# CPU-board-Sheet1-multi.net
KiCad netlist of a schematic drawn in Altium Designer
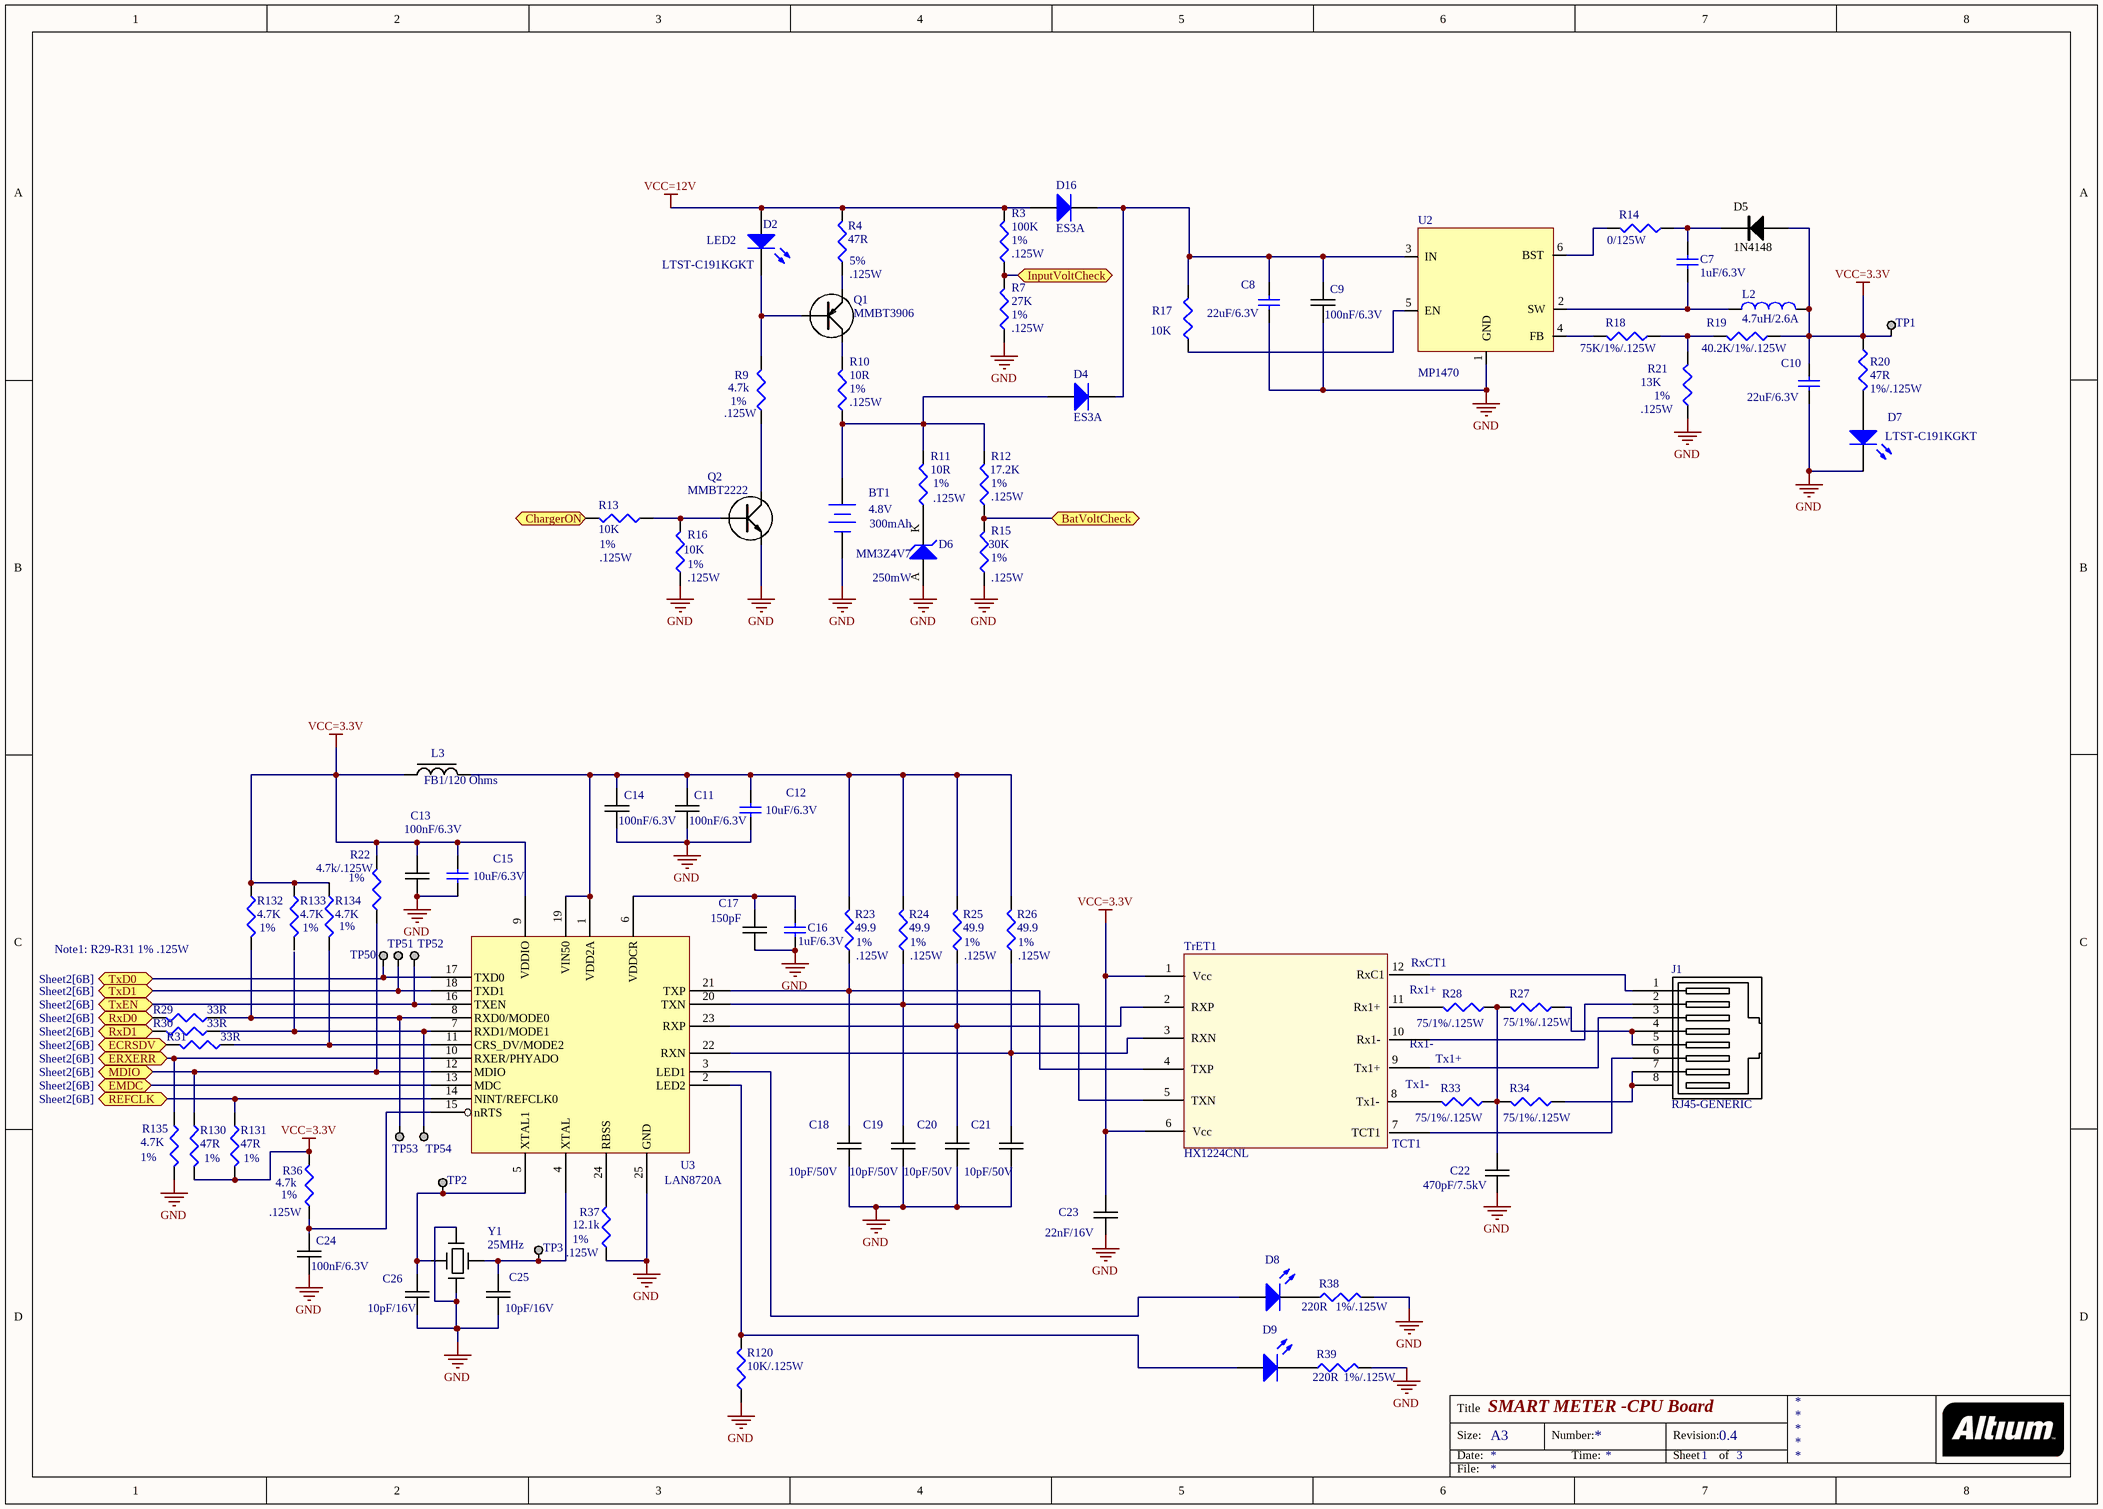
[diagram p0: CPU-board-Sheet1-multi.SchDoc]

(export (version "E")
  (design (tool "Eeschema 10.0.6"))
  (components
    (comp (ref "BT1")
      (value "4.8V")
      (footprint "BAT-2")
      (description "Multicell Battery")
      (fields
        (field (name "MANUFACTURER") "Guangdong, China (Mainland)")
        (field (name "PUBLISHER") "sunbangpower.en.alibaba.com")
      )
      (libsource (lib "Miscellaneous Devices") (part "Battery"))
    )
    (comp (ref "C7")
      (value "1uF/6.3V")
      (footprint "0402C-GENERIC")
      (description "Capacitor")
      (fields (field (name "MANUFACTURER") "Murata") (field (name "PUBLISHER") "Altium Limited"))
      (libsource (lib "Miscellaneous Devices") (part "Cap"))
    )
    (comp (ref "C8")
      (value "22uF/6.3V")
      (footprint "1206C-GENERIC")
      (description "Capacitor")
      (fields (field (name "MANUFACTURER") "Murata") (field (name "PUBLISHER") "Altium Limited"))
      (libsource (lib "Miscellaneous Devices") (part "Cap"))
    )
    (comp (ref "C9")
      (value "100nF/6.3V")
      (footprint "0402C-GENERIC")
      (description "CAPACITOR 0805 CERAMIC")
      (fields (field (name "MANUFACTURER") "Taiyo Yuden"))
      (libsource (lib "vh_altium_library") (part "0805C-18PF-50V-C0G-JOH"))
    )
    (comp (ref "C10")
      (value "22uF/6.3V")
      (footprint "1206C-GENERIC")
      (description "Capacitor")
      (fields (field (name "MANUFACTURER") "Murata") (field (name "PUBLISHER") "Altium Limited"))
      (libsource (lib "Miscellaneous Devices") (part "Cap"))
    )
    (comp (ref "C11")
      (value "100nF/6.3V")
      (footprint "0402C-GENERIC")
      (description "CAPACITOR 0805 CERAMIC")
      (fields (field (name "MANUFACTURER") "Taiyo Yuden"))
      (libsource (lib "vh_altium_library") (part "0805C-18PF-50V-C0G-JOH"))
    )
    (comp (ref "C12")
      (value "10uF/6.3V")
      (footprint "0402C-GENERIC")
      (description "Capacitor")
      (fields (field (name "MANUFACTURER") "Murata") (field (name "PUBLISHER") "Altium Limited"))
      (libsource (lib "Miscellaneous Devices") (part "Cap"))
    )
    (comp (ref "C13")
      (value "100nF/6.3V")
      (footprint "0402C-GENERIC")
      (description "CAPACITOR 0805 CERAMIC")
      (fields (field (name "MANUFACTURER") "Taiyo Yuden"))
      (libsource (lib "vh_altium_library") (part "0805C-18PF-50V-C0G-JOH"))
    )
    (comp (ref "C14")
      (value "100nF/6.3V")
      (footprint "0402C-GENERIC")
      (description "CAPACITOR 0805 CERAMIC")
      (fields (field (name "MANUFACTURER") "Taiyo Yuden"))
      (libsource (lib "vh_altium_library") (part "0805C-18PF-50V-C0G-JOH"))
    )
    (comp (ref "C15")
      (value "10uF/6.3V")
      (footprint "0402C-GENERIC")
      (description "Capacitor")
      (fields (field (name "MANUFACTURER") "Murata") (field (name "PUBLISHER") "Altium Limited"))
      (libsource (lib "Miscellaneous Devices") (part "Cap"))
    )
    (comp (ref "C16")
      (value "1uF/6.3V")
      (footprint "0402C-GENERIC")
      (description "Capacitor")
      (fields (field (name "MANUFACTURER") "Murata") (field (name "PUBLISHER") "Altium Limited"))
      (libsource (lib "Miscellaneous Devices") (part "Cap"))
    )
    (comp (ref "C17")
      (value "150pF")
      (footprint "0402C-GENERIC")
      (description "CAPACITOR 0805 CERAMIC")
      (fields (field (name "MANUFACTURER") "Wurth Electronics"))
      (libsource (lib "vh_altium_library") (part "0805C-18PF-50V-C0G-JOH"))
    )
    (comp (ref "C18")
      (value "10pF/50V")
      (footprint "0402C-GENERIC")
      (description "CAPACITOR 0805 CERAMIC")
      (fields (field (name "MANUFACTURER") "Murata"))
      (libsource (lib "vh_altium_library") (part "0805C-18PF-50V-C0G-JOH"))
    )
    (comp (ref "C19")
      (value "10pF/50V")
      (footprint "0402C-GENERIC")
      (description "CAPACITOR 0805 CERAMIC")
      (fields (field (name "MANUFACTURER") "Murata"))
      (libsource (lib "vh_altium_library") (part "0805C-18PF-50V-C0G-JOH"))
    )
    (comp (ref "C20")
      (value "10pF/50V")
      (footprint "0402C-GENERIC")
      (description "CAPACITOR 0805 CERAMIC")
      (fields (field (name "MANUFACTURER") "Murata"))
      (libsource (lib "vh_altium_library") (part "0805C-18PF-50V-C0G-JOH"))
    )
    (comp (ref "C21")
      (value "10pF/50V")
      (footprint "0402C-GENERIC")
      (description "CAPACITOR 0805 CERAMIC")
      (fields (field (name "MANUFACTURER") "Murata"))
      (libsource (lib "vh_altium_library") (part "0805C-18PF-50V-C0G-JOH"))
    )
    (comp (ref "C22")
      (value "470pF/7.5kV")
      (footprint "1808")
      (description "CAPACITOR 1808CERAMIC")
      (fields (field (name "MANUFACTURER") "Murata"))
      (libsource (lib "vh_altium_library") (part "0805C-18PF-50V-C0G-JOH"))
    )
    (comp (ref "C23")
      (value "22nF/16V")
      (footprint "0402C-GENERIC")
      (description "CAPACITOR 0805 CERAMIC")
      (fields (field (name "MANUFACTURER") "Murata Electronics"))
      (libsource (lib "vh_altium_library") (part "0805C-18PF-50V-C0G-JOH"))
    )
    (comp (ref "C24")
      (value "100nF/6.3V")
      (footprint "0402C-GENERIC")
      (description "CAPACITOR 0805 CERAMIC")
      (fields (field (name "MANUFACTURER") "Taiyo Yuden"))
      (libsource (lib "vh_altium_library") (part "0805C-18PF-50V-C0G-JOH"))
    )
    (comp (ref "C25")
      (value "10pF/16V")
      (footprint "0402C-GENERIC")
      (description "CAPACITOR 0805 CERAMIC")
      (fields (field (name "MANUFACTURER") "Murata"))
      (libsource (lib "vh_altium_library") (part "0805C-18PF-50V-C0G-JOH"))
    )
    (comp (ref "C26")
      (value "10pF/16V")
      (footprint "0402C-GENERIC")
      (description "CAPACITOR 0805 CERAMIC")
      (fields (field (name "MANUFACTURER") "Murata"))
      (libsource (lib "vh_altium_library") (part "0805C-18PF-50V-C0G-JOH"))
    )
    (comp (ref "D2")
      (value "LED2")
      (footprint "LED-SM")
      (description "Typical RED, GREEN, YELLOW, AMBER GaAs LED")
      (fields (field (name "MANUFACTURER") "Lite-On Inc") (field (name "PUBLISHER") "Altium Limited"))
      (libsource (lib "Miscellaneous Devices") (part "LED2"))
    )
    (comp (ref "D4")
      (value "ES3A")
      (footprint "DO214AA")
      (description "1 Amp General Purpose Rectifier")
      (fields (field (name "MANUFACTURER") "Fairchild Co") (field (name "PUBLISHER") "Altium Limited"))
      (libsource (lib "Miscellaneous Devices") (part "Diode 1N4007"))
    )
    (comp (ref "D5")
      (value "1N4148")
      (footprint "SOD-123")
      (description "1N4001")
      (fields (field (name "MANUFACTURER") "Vishay"))
      (libsource (lib "vh_altium_library") (part "1N4001"))
    )
    (comp (ref "D6")
      (value "MM3Z4V7")
      (footprint "SOT23-DIODE")
      (description "Zener Diode")
      (fields (field (name "MANUFACTURER") "Fairchild Semi") (field (name "PUBLISHER") "Altium Limited"))
      (libsource (lib "Miscellaneous Devices") (part "D Zener"))
    )
    (comp (ref "D7")
      (value "LED2")
      (footprint "LED-SM")
      (description "Typical RED, GREEN, YELLOW, AMBER GaAs LED")
      (fields (field (name "MANUFACTURER") "Lite-On Inc") (field (name "PUBLISHER") "Altium Limited"))
      (libsource (lib "Miscellaneous Devices") (part "LED2"))
    )
    (comp (ref "D8")
      (value "LED2")
      (footprint "LED-SM")
      (description "Typical RED, GREEN, YELLOW, AMBER GaAs LED")
      (fields (field (name "MANUFACTURER") "Lite-On Inc") (field (name "PUBLISHER") "Altium Limited"))
      (libsource (lib "Miscellaneous Devices") (part "LED2"))
    )
    (comp (ref "D9")
      (value "LED2")
      (footprint "LED-SM")
      (description "Typical RED, GREEN, YELLOW, AMBER GaAs LED")
      (fields (field (name "MANUFACTURER") "Lite-On Inc") (field (name "PUBLISHER") "Altium Limited"))
      (libsource (lib "Miscellaneous Devices") (part "LED2"))
    )
    (comp (ref "D16")
      (value "ES3A")
      (footprint "DO214AA")
      (description "1 Amp General Purpose Rectifier")
      (fields (field (name "MANUFACTURER") "Fairchild Co") (field (name "PUBLISHER") "Altium Limited"))
      (libsource (lib "Miscellaneous Devices") (part "Diode 1N4007"))
    )
    (comp (ref "J1")
      (value "RJ45-GENERIC")
      (footprint "RJ45-8/8")
      (description "GENERIC RJ45 CONNECTOR 8 PIN")
      (fields (field (name "MANUFACTURER") "Assman WSW Components"))
      (libsource (lib "vh_altium_library") (part "RJ45-GENERIC"))
    )
    (comp (ref "L2")
      (value "4.7uH/2.6A")
      (footprint "Inductor 4.7/6.8")
      (description "Inductor")
      (fields (field (name "MANUFACTURER") "Bourns") (field (name "PUBLISHER") "Altium Limited"))
      (libsource (lib "Miscellaneous Devices") (part "Inductor"))
    )
    (comp (ref "L3")
      (value "FB1/120 Ohms")
      (footprint "0603C-2U2")
      (description "1239AS-H-1R0N")
      (fields (field (name "MANUFACTURER") "Murata Electronics"))
      (libsource (lib "SMD Magnetics-SM") (part "1U-1239AS-TOKO"))
    )
    (comp (ref "Q1")
      (value "MMBT3906")
      (footprint "SOT23-BCE")
      (description "GENERIC PNP BIPOLAR TRANSISTOR")
      (fields (field (name "MANUFACTURER") "On Semi"))
      (libsource (lib "generic") (part "PNP-GENERIC"))
    )
    (comp (ref "Q2")
      (value "MMBT2222")
      (footprint "MMBT2222")
      (description "BC847 SMALL SIGNAL NPN TRANSISTOR")
      (fields (field (name "MANUFACTURER") "Diodes  Inc."))
      (libsource (lib "vh_altium_library") (part "MMBT2222"))
    )
    (comp (ref "R3")
      (value "100K")
      (footprint "0402R-TBD")
      (description "Resistor")
      (fields (field (name "MANUFACTURER") "Panasonic") (field (name "PUBLISHER") "Altium Limited"))
      (libsource (lib "Miscellaneous Devices") (part "Res3"))
    )
    (comp (ref "R4")
      (value "47R")
      (footprint "0402R-TBD")
      (description "Resistor")
      (fields (field (name "PUBLISHER") "Altium Limited"))
      (libsource (lib "Miscellaneous Devices") (part "Res3"))
    )
    (comp (ref "R7")
      (value "27K")
      (footprint "0402R-TBD")
      (description "Resistor")
      (fields (field (name "MANUFACTURER") "Panasonic") (field (name "PUBLISHER") "Altium Limited"))
      (libsource (lib "Miscellaneous Devices") (part "Res3"))
    )
    (comp (ref "R9")
      (value "4.7k")
      (footprint "0402R-TBD")
      (description "Resistor")
      (fields (field (name "MANUFACTURER") "Panasonic") (field (name "PUBLISHER") "Altium Limited"))
      (libsource (lib "Miscellaneous Devices") (part "Res3"))
    )
    (comp (ref "R10")
      (value "10R")
      (footprint "0402R-TBD")
      (description "Resistor")
      (fields (field (name "MANUFACTURER") "Panasonic") (field (name "PUBLISHER") "Altium Limited"))
      (libsource (lib "Miscellaneous Devices") (part "Res3"))
    )
    (comp (ref "R11")
      (value "10R")
      (footprint "0402R-TBD")
      (description "Resistor")
      (fields (field (name "MANUFACTURER") "Panasonic") (field (name "PUBLISHER") "Altium Limited"))
      (libsource (lib "Miscellaneous Devices") (part "Res3"))
    )
    (comp (ref "R12")
      (value "17.2K")
      (footprint "0402R-TBD")
      (description "Resistor")
      (fields (field (name "MANUFACTURER") "Vishay Dale") (field (name "PUBLISHER") "Altium Limited"))
      (libsource (lib "Miscellaneous Devices") (part "Res3"))
    )
    (comp (ref "R13")
      (value "10K")
      (footprint "0402R-TBD")
      (description "Resistor")
      (fields (field (name "MANUFACTURER") "Panasonic") (field (name "PUBLISHER") "Altium Limited"))
      (libsource (lib "Miscellaneous Devices") (part "Res3"))
    )
    (comp (ref "R14")
      (value "0/125W")
      (footprint "0402C-GENERIC")
      (description "Resistor")
      (fields (field (name "MANUFACTURER") "Vishay Dale") (field (name "PUBLISHER") "Altium Limited"))
      (libsource (lib "Miscellaneous Devices") (part "Res3"))
    )
    (comp (ref "R15")
      (value "30K")
      (footprint "0402R-TBD")
      (description "Resistor")
      (fields (field (name "MANUFACTURER") "Panasonic") (field (name "PUBLISHER") "Altium Limited"))
      (libsource (lib "Miscellaneous Devices") (part "Res3"))
    )
    (comp (ref "R16")
      (value "10K")
      (footprint "0402R-TBD")
      (description "Resistor")
      (fields (field (name "MANUFACTURER") "Panasonic") (field (name "PUBLISHER") "Altium Limited"))
      (libsource (lib "Miscellaneous Devices") (part "Res3"))
    )
    (comp (ref "R17")
      (value "10K")
      (footprint "0402R-TBD")
      (description "Resistor")
      (fields (field (name "MANUFACTURER") "Panasonic") (field (name "PUBLISHER") "Altium Limited"))
      (libsource (lib "Miscellaneous Devices") (part "Res3"))
    )
    (comp (ref "R18")
      (value "75K/1%/.125W")
      (footprint "0402C-TBD")
      (description "Resistor")
      (fields (field (name "MANUFACTURER") "Panasonic") (field (name "PUBLISHER") "Altium Limited"))
      (libsource (lib "Miscellaneous Devices") (part "Res3"))
    )
    (comp (ref "R19")
      (value "40.2K/1%/.125W")
      (footprint "0402R-TBD")
      (description "Resistor")
      (fields (field (name "MANUFACTURER") "Panasonic") (field (name "PUBLISHER") "Altium Limited"))
      (libsource (lib "Miscellaneous Devices") (part "Res3"))
    )
    (comp (ref "R20")
      (value "47R")
      (footprint "0402R-TBD")
      (description "Resistor")
      (fields (field (name "PUBLISHER") "Altium Limited"))
      (libsource (lib "Miscellaneous Devices") (part "Res3"))
    )
    (comp (ref "R21")
      (value "13K")
      (footprint "0402R-TBD")
      (description "Resistor")
      (fields (field (name "MANUFACTURER") "Panasonic") (field (name "PUBLISHER") "Altium Limited"))
      (libsource (lib "Miscellaneous Devices") (part "Res3"))
    )
    (comp (ref "R22")
      (value "4.7k/.125W")
      (footprint "0402R-TBD")
      (description "Resistor")
      (fields (field (name "MANUFACTURER") "Panasonic") (field (name "PUBLISHER") "Altium Limited"))
      (libsource (lib "Miscellaneous Devices") (part "Res3"))
    )
    (comp (ref "R23")
      (value "49.9")
      (footprint "0402R-TBD")
      (description "Resistor")
      (fields (field (name "MANUFACTURER") "Panasonic") (field (name "PUBLISHER") "Altium Limited"))
      (libsource (lib "Miscellaneous Devices") (part "Res3"))
    )
    (comp (ref "R24")
      (value "49.9")
      (footprint "0402R-TBD")
      (description "Resistor")
      (fields (field (name "MANUFACTURER") "Panasonic") (field (name "PUBLISHER") "Altium Limited"))
      (libsource (lib "Miscellaneous Devices") (part "Res3"))
    )
    (comp (ref "R25")
      (value "49.9")
      (footprint "0402R-TBD")
      (description "Resistor")
      (fields (field (name "MANUFACTURER") "Panasonic") (field (name "PUBLISHER") "Altium Limited"))
      (libsource (lib "Miscellaneous Devices") (part "Res3"))
    )
    (comp (ref "R26")
      (value "49.9")
      (footprint "0402R-TBD")
      (description "Resistor")
      (fields (field (name "MANUFACTURER") "Panasonic") (field (name "PUBLISHER") "Altium Limited"))
      (libsource (lib "Miscellaneous Devices") (part "Res3"))
    )
    (comp (ref "R27")
      (value "75/1%/.125W")
      (footprint "0402R-TBD")
      (description "Resistor")
      (fields (field (name "MANUFACTURER") "Panasonic") (field (name "PUBLISHER") "Altium Limited"))
      (libsource (lib "Miscellaneous Devices") (part "Res3"))
    )
    (comp (ref "R28")
      (value "75/1%/.125W")
      (footprint "0402R-TBD")
      (description "Resistor")
      (fields (field (name "MANUFACTURER") "Panasonic") (field (name "PUBLISHER") "Altium Limited"))
      (libsource (lib "Miscellaneous Devices") (part "Res3"))
    )
    (comp (ref "R29")
      (value "33R")
      (footprint "0402R-TBD")
      (description "Resistor")
      (fields (field (name "MANUFACTURER") "Panasonic") (field (name "PUBLISHER") "Altium Limited"))
      (libsource (lib "Miscellaneous Devices") (part "Res3"))
    )
    (comp (ref "R30")
      (value "33R")
      (footprint "0402R-TBD")
      (description "Resistor")
      (fields (field (name "MANUFACTURER") "Panasonic") (field (name "PUBLISHER") "Altium Limited"))
      (libsource (lib "Miscellaneous Devices") (part "Res3"))
    )
    (comp (ref "R31")
      (value "33R")
      (footprint "0402R-TBD")
      (description "Resistor")
      (fields (field (name "MANUFACTURER") "Panasonic") (field (name "PUBLISHER") "Altium Limited"))
      (libsource (lib "Miscellaneous Devices") (part "Res3"))
    )
    (comp (ref "R33")
      (value "75/1%/.125W")
      (footprint "0402R-TBD")
      (description "Resistor")
      (fields (field (name "MANUFACTURER") "Panasonic") (field (name "PUBLISHER") "Altium Limited"))
      (libsource (lib "Miscellaneous Devices") (part "Res3"))
    )
    (comp (ref "R34")
      (value "75/1%/.125W")
      (footprint "0402R-TBD")
      (description "Resistor")
      (fields (field (name "MANUFACTURER") "Panasonic") (field (name "PUBLISHER") "Altium Limited"))
      (libsource (lib "Miscellaneous Devices") (part "Res3"))
    )
    (comp (ref "R36")
      (value "4.7k")
      (footprint "0402R-TBD")
      (description "Resistor")
      (fields (field (name "MANUFACTURER") "Panasonic") (field (name "PUBLISHER") "Altium Limited"))
      (libsource (lib "Miscellaneous Devices") (part "Res3"))
    )
    (comp (ref "R37")
      (value "12.1k")
      (footprint "0402R-TBD")
      (description "Resistor")
      (fields (field (name "MANUFACTURER") "Panasonic") (field (name "PUBLISHER") "Altium Limited"))
      (libsource (lib "Miscellaneous Devices") (part "Res3"))
    )
    (comp (ref "R38")
      (value "220R")
      (footprint "0402R-TBD")
      (description "Resistor")
      (fields (field (name "MANUFACTURER") "Panasonic") (field (name "PUBLISHER") "Altium Limited"))
      (libsource (lib "Miscellaneous Devices") (part "Res3"))
    )
    (comp (ref "R39")
      (value "220R")
      (footprint "0402R-TBD")
      (description "Resistor")
      (fields (field (name "MANUFACTURER") "Panasonic") (field (name "PUBLISHER") "Altium Limited"))
      (libsource (lib "Miscellaneous Devices") (part "Res3"))
    )
    (comp (ref "R120")
      (value "10K/.125W")
      (footprint "0402R-TBD")
      (description "Resistor")
      (fields (field (name "MANUFACTURER") "Panasonic") (field (name "PUBLISHER") "Altium Limited"))
      (libsource (lib "Miscellaneous Devices") (part "Res3"))
    )
    (comp (ref "R130")
      (value "47R")
      (footprint "0402R-TBD")
      (description "Resistor")
      (fields (field (name "MANUFACTURER") "Panasonic") (field (name "PUBLISHER") "Altium Limited"))
      (libsource (lib "Miscellaneous Devices") (part "Res3"))
    )
    (comp (ref "R131")
      (value "47R")
      (footprint "0402R-TBD")
      (description "Resistor")
      (fields (field (name "MANUFACTURER") "Panasonic") (field (name "PUBLISHER") "Altium Limited"))
      (libsource (lib "Miscellaneous Devices") (part "Res3"))
    )
    (comp (ref "R132")
      (value "4.7K")
      (footprint "0402R-TBD")
      (description "Resistor")
      (fields (field (name "MANUFACTURER") "Panasonic") (field (name "PUBLISHER") "Altium Limited"))
      (libsource (lib "Miscellaneous Devices") (part "Res3"))
    )
    (comp (ref "R133")
      (value "4.7K")
      (footprint "0402R-TBD")
      (description "Resistor")
      (fields (field (name "MANUFACTURER") "Panasonic") (field (name "PUBLISHER") "Altium Limited"))
      (libsource (lib "Miscellaneous Devices") (part "Res3"))
    )
    (comp (ref "R134")
      (value "4.7K")
      (footprint "0402R-TBD")
      (description "Resistor")
      (fields (field (name "MANUFACTURER") "Panasonic") (field (name "PUBLISHER") "Altium Limited"))
      (libsource (lib "Miscellaneous Devices") (part "Res3"))
    )
    (comp (ref "R135")
      (value "4.7K")
      (footprint "0402R-TBD")
      (description "Resistor")
      (fields (field (name "MANUFACTURER") "Panasonic") (field (name "PUBLISHER") "Altium Limited"))
      (libsource (lib "Miscellaneous Devices") (part "Res3"))
    )
    (comp (ref "TP1")
      (value "TESTPOINT")
      (footprint "TESTPOINT")
      (description "TESTPOINT SCOPE GRABBER")
      (fields
        (field (name "MANUFACTURER PART NUMBER") "5010")
        (field (name "MANUFACTURER") "Keystone Electronics")
      )
      (libsource (lib "vh_altium_library") (part "TESTPOINT"))
    )
    (comp (ref "TP2")
      (value "TESTPOINT")
      (footprint "TESTPOINT")
      (description "TESTPOINT SCOPE GRABBER")
      (fields
        (field (name "MANUFACTURER PART NUMBER") "5010")
        (field (name "MANUFACTURER") "Keystone Electronics")
      )
      (libsource (lib "vh_altium_library") (part "TESTPOINT"))
    )
    (comp (ref "TP3")
      (value "TESTPOINT")
      (footprint "TESTPOINT")
      (description "TESTPOINT SCOPE GRABBER")
      (fields
        (field (name "MANUFACTURER PART NUMBER") "5010")
        (field (name "MANUFACTURER") "Keystone Electronics")
      )
      (libsource (lib "vh_altium_library") (part "TESTPOINT"))
    )
    (comp (ref "TP50")
      (value "TESTPOINT")
      (footprint "TESTPOINT")
      (description "TESTPOINT SCOPE GRABBER")
      (fields
        (field (name "MANUFACTURER PART NUMBER") "5010")
        (field (name "MANUFACTURER") "Keystone Electronics")
      )
      (libsource (lib "vh_altium_library") (part "TESTPOINT"))
    )
    (comp (ref "TP51")
      (value "TESTPOINT")
      (footprint "TESTPOINT")
      (description "TESTPOINT SCOPE GRABBER")
      (fields
        (field (name "MANUFACTURER PART NUMBER") "5010")
        (field (name "MANUFACTURER") "Keystone Electronics")
      )
      (libsource (lib "vh_altium_library") (part "TESTPOINT"))
    )
    (comp (ref "TP52")
      (value "TESTPOINT")
      (footprint "TESTPOINT")
      (description "TESTPOINT SCOPE GRABBER")
      (fields
        (field (name "MANUFACTURER PART NUMBER") "5010")
        (field (name "MANUFACTURER") "Keystone Electronics")
      )
      (libsource (lib "vh_altium_library") (part "TESTPOINT"))
    )
    (comp (ref "TP53")
      (value "TESTPOINT")
      (footprint "TESTPOINT")
      (description "TESTPOINT SCOPE GRABBER")
      (fields
        (field (name "MANUFACTURER PART NUMBER") "5010")
        (field (name "MANUFACTURER") "Keystone Electronics")
      )
      (libsource (lib "vh_altium_library") (part "TESTPOINT"))
    )
    (comp (ref "TP54")
      (value "TESTPOINT")
      (footprint "TESTPOINT")
      (description "TESTPOINT SCOPE GRABBER")
      (fields
        (field (name "MANUFACTURER PART NUMBER") "5010")
        (field (name "MANUFACTURER") "Keystone Electronics")
      )
      (libsource (lib "vh_altium_library") (part "TESTPOINT"))
    )
    (comp (ref "TrET1") (value "HX1224CNL") (libsource (lib "SMLib") (part "hx1224nl")))
    (comp (ref "U2")
      (value "MP1470")
      (footprint "MP1470")
      (fields (field (name "MANUFACTURER") "MPS Inc"))
      (libsource (lib "SMLib") (part "MP1470"))
    )
    (comp (ref "U3")
      (value "LAN8720A")
      (footprint "Atmel Multimedia:QFN24_4X4_N")
      (fields (field (name "MANUFACTURER") "Microchip"))
      (libsource (lib "SMLib") (part "LAN8720"))
    )
    (comp (ref "Y1")
      (value "25MHz")
      (footprint "CeramicResonator8-16MHZ")
      (description "25MHz CRYSTAL HC49US SHORT BODY")
      (fields (field (name "MANUFACTURER") "KDS DAISHINKU.Corp"))
      (libsource (lib "Crystals") (part "12MC-HC49US-7MM"))
    )
  )
  (nets
    (net (code "1") (name "/BatVoltCheck") (class "Default")
      (node (ref "R12") (pin "1") (pinfunction "1_1") (pintype "passive"))
      (node (ref "R15") (pin "2") (pinfunction "2_2") (pintype "passive"))
    )
    (net (code "2") (name "/ChargerON") (class "Default")
      (node (ref "R13") (pin "2") (pinfunction "2_2") (pintype "passive"))
    )
    (net (code "3") (name "/ECRSDV") (class "Default")
      (node (ref "R31") (pin "2") (pinfunction "2_2") (pintype "passive"))
    )
    (net (code "4") (name "/EMDC") (class "Default")
      (node (ref "U3") (pin "13") (pinfunction "MDC_13") (pintype "passive"))
    )
    (net (code "5") (name "/ERXERR") (class "Default")
      (node (ref "R135") (pin "1") (pinfunction "1_1") (pintype "passive"))
      (node (ref "U3") (pin "10") (pinfunction "RXER/PHYADO_10") (pintype "passive"))
    )
    (net (code "6") (name "/InputVoltCheck") (class "Default")
      (node (ref "R3") (pin "1") (pinfunction "1_1") (pintype "passive"))
      (node (ref "R7") (pin "2") (pinfunction "2_2") (pintype "passive"))
    )
    (net (code "7") (name "/MDIO") (class "Default")
      (node (ref "R130") (pin "1") (pinfunction "1_1") (pintype "passive"))
      (node (ref "R22") (pin "1") (pinfunction "1_1") (pintype "passive"))
      (node (ref "U3") (pin "12") (pinfunction "MDIO_12") (pintype "passive"))
    )
    (net (code "8") (name "/REFCLK") (class "Default")
      (node (ref "R131") (pin "1") (pinfunction "1_1") (pintype "passive"))
      (node (ref "U3") (pin "14") (pinfunction "NINT/REFCLK0_14") (pintype "passive"))
    )
    (net (code "9") (name "/RxD0") (class "Default")
      (node (ref "R29") (pin "2") (pinfunction "2_2") (pintype "passive"))
    )
    (net (code "10") (name "/RxD1") (class "Default")
      (node (ref "R30") (pin "2") (pinfunction "2_2") (pintype "passive"))
    )
    (net (code "11") (name "/TxD0") (class "Default")
      (node (ref "TP50") (pin "1") (pinfunction "1_1") (pintype "passive"))
      (node (ref "U3") (pin "17") (pinfunction "TXD0_17") (pintype "passive"))
    )
    (net (code "12") (name "/TxD1") (class "Default")
      (node (ref "TP51") (pin "1") (pinfunction "1_1") (pintype "passive"))
      (node (ref "U3") (pin "18") (pinfunction "TXD1_18") (pintype "passive"))
    )
    (net (code "13") (name "/TxEN") (class "Default")
      (node (ref "TP52") (pin "1") (pinfunction "1_1") (pintype "passive"))
      (node (ref "U3") (pin "16") (pinfunction "TXEN_16") (pintype "passive"))
    )
    (net (code "14") (name "GND") (class "Default")
      (node (ref "BT1") (pin "2") (pinfunction "-_2") (pintype "passive"))
      (node (ref "C10") (pin "2") (pinfunction "2_2") (pintype "passive"))
      (node (ref "C11") (pin "2") (pintype "passive"))
      (node (ref "C12") (pin "2") (pinfunction "2_2") (pintype "passive"))
      (node (ref "C13") (pin "2") (pintype "passive"))
      (node (ref "C14") (pin "2") (pintype "passive"))
      (node (ref "C15") (pin "2") (pinfunction "2_2") (pintype "passive"))
      (node (ref "C16") (pin "1") (pinfunction "1_1") (pintype "passive"))
      (node (ref "C17") (pin "2") (pintype "passive"))
      (node (ref "C18") (pin "2") (pintype "passive"))
      (node (ref "C19") (pin "2") (pintype "passive"))
      (node (ref "C20") (pin "2") (pintype "passive"))
      (node (ref "C21") (pin "2") (pintype "passive"))
      (node (ref "C22") (pin "2") (pintype "passive"))
      (node (ref "C23") (pin "2") (pintype "passive"))
      (node (ref "C24") (pin "2") (pintype "passive"))
      (node (ref "C25") (pin "2") (pintype "passive"))
      (node (ref "C26") (pin "2") (pintype "passive"))
      (node (ref "C8") (pin "2") (pinfunction "2_2") (pintype "passive"))
      (node (ref "C9") (pin "2") (pintype "passive"))
      (node (ref "D6") (pin "A") (pinfunction "A_A") (pintype "passive"))
      (node (ref "D7") (pin "2") (pinfunction "K_2") (pintype "passive"))
      (node (ref "Q2") (pin "E") (pintype "passive"))
      (node (ref "R120") (pin "1") (pinfunction "1_1") (pintype "passive"))
      (node (ref "R135") (pin "2") (pinfunction "2_2") (pintype "passive"))
      (node (ref "R15") (pin "1") (pinfunction "1_1") (pintype "passive"))
      (node (ref "R16") (pin "1") (pinfunction "1_1") (pintype "passive"))
      (node (ref "R21") (pin "1") (pinfunction "1_1") (pintype "passive"))
      (node (ref "R37") (pin "1") (pinfunction "1_1") (pintype "passive"))
      (node (ref "R38") (pin "2") (pinfunction "2_2") (pintype "passive"))
      (node (ref "R39") (pin "2") (pinfunction "2_2") (pintype "passive"))
      (node (ref "R7") (pin "1") (pinfunction "1_1") (pintype "passive"))
      (node (ref "U2") (pin "1") (pinfunction "GND_1") (pintype "passive"))
      (node (ref "U3") (pin "25") (pinfunction "GND_25") (pintype "passive"))
      (node (ref "Y1") (pin "2") (pintype "passive"))
      (node (ref "Y1") (pin "4") (pintype "passive"))
    )
    (net (code "15") (name "Net-(BT1-+)") (class "Default")
      (node (ref "BT1") (pin "1") (pinfunction "+_1") (pintype "passive"))
      (node (ref "D4") (pin "1") (pinfunction "A_1") (pintype "passive"))
      (node (ref "R10") (pin "1") (pinfunction "1_1") (pintype "passive"))
      (node (ref "R11") (pin "2") (pinfunction "2_2") (pintype "passive"))
      (node (ref "R12") (pin "2") (pinfunction "2_2") (pintype "passive"))
    )
    (net (code "16") (name "Net-(C7-Pad2)") (class "Default")
      (node (ref "C7") (pin "2") (pinfunction "2_2") (pintype "passive"))
      (node (ref "D5") (pin "K") (pinfunction "K_K") (pintype "passive"))
      (node (ref "R14") (pin "1") (pinfunction "1_1") (pintype "passive"))
    )
    (net (code "17") (name "Net-(C22-Pad1)") (class "Default")
      (node (ref "C22") (pin "1") (pintype "passive"))
      (node (ref "R27") (pin "2") (pinfunction "2_2") (pintype "passive"))
      (node (ref "R28") (pin "1") (pinfunction "1_1") (pintype "passive"))
      (node (ref "R33") (pin "1") (pinfunction "1_1") (pintype "passive"))
      (node (ref "R34") (pin "2") (pinfunction "2_2") (pintype "passive"))
    )
    (net (code "18") (name "Net-(D2-K)") (class "Default")
      (node (ref "D2") (pin "2") (pinfunction "K_2") (pintype "passive"))
      (node (ref "Q1") (pin "B") (pintype "passive"))
      (node (ref "R9") (pin "2") (pinfunction "2_2") (pintype "passive"))
    )
    (net (code "19") (name "Net-(D6-PadK)") (class "Default")
      (node (ref "D6") (pin "K") (pinfunction "K_K") (pintype "passive"))
      (node (ref "R11") (pin "1") (pinfunction "1_1") (pintype "passive"))
    )
    (net (code "20") (name "Net-(D7-A)") (class "Default")
      (node (ref "D7") (pin "1") (pinfunction "A_1") (pintype "passive"))
      (node (ref "R20") (pin "2") (pinfunction "2_2") (pintype "passive"))
    )
    (net (code "21") (name "Net-(D8-A)") (class "Default")
      (node (ref "D8") (pin "1") (pinfunction "A_1") (pintype "passive"))
      (node (ref "U3") (pin "3") (pinfunction "LED1_3") (pintype "passive"))
    )
    (net (code "22") (name "Net-(D8-K)") (class "Default")
      (node (ref "D8") (pin "2") (pinfunction "K_2") (pintype "passive"))
      (node (ref "R38") (pin "1") (pinfunction "1_1") (pintype "passive"))
    )
    (net (code "23") (name "Net-(D9-A)") (class "Default")
      (node (ref "D9") (pin "1") (pinfunction "A_1") (pintype "passive"))
      (node (ref "R120") (pin "2") (pinfunction "2_2") (pintype "passive"))
      (node (ref "U3") (pin "2") (pinfunction "LED2_2") (pintype "passive"))
    )
    (net (code "24") (name "Net-(D9-K)") (class "Default")
      (node (ref "D9") (pin "2") (pinfunction "K_2") (pintype "passive"))
      (node (ref "R39") (pin "1") (pinfunction "1_1") (pintype "passive"))
    )
    (net (code "25") (name "Net-(D16-K)") (class "Default")
      (node (ref "C8") (pin "1") (pinfunction "1_1") (pintype "passive"))
      (node (ref "C9") (pin "1") (pintype "passive"))
      (node (ref "D16") (pin "2") (pinfunction "K_2") (pintype "passive"))
      (node (ref "D4") (pin "2") (pinfunction "K_2") (pintype "passive"))
      (node (ref "R17") (pin "2") (pinfunction "2_2") (pintype "passive"))
      (node (ref "U2") (pin "3") (pinfunction "IN_3") (pintype "passive"))
    )
    (net (code "26") (name "Net-(J1-Pad4)") (class "Default")
      (node (ref "J1") (pin "4") (pintype "passive"))
      (node (ref "J1") (pin "5") (pintype "passive"))
      (node (ref "R27") (pin "1") (pinfunction "1_1") (pintype "passive"))
    )
    (net (code "27") (name "Net-(J1-Pad7)") (class "Default")
      (node (ref "J1") (pin "7") (pintype "passive"))
      (node (ref "J1") (pin "8") (pintype "passive"))
      (node (ref "R34") (pin "1") (pinfunction "1_1") (pintype "passive"))
    )
    (net (code "28") (name "Net-(Q1-PadC)") (class "Default")
      (node (ref "Q1") (pin "C") (pintype "passive"))
      (node (ref "R10") (pin "2") (pinfunction "2_2") (pintype "passive"))
    )
    (net (code "29") (name "Net-(Q1-PadE)") (class "Default")
      (node (ref "Q1") (pin "E") (pintype "passive"))
      (node (ref "R4") (pin "1") (pinfunction "1_1") (pintype "passive"))
    )
    (net (code "30") (name "Net-(Q2-PadB)") (class "Default")
      (node (ref "Q2") (pin "B") (pintype "passive"))
      (node (ref "R13") (pin "1") (pinfunction "1_1") (pintype "passive"))
      (node (ref "R16") (pin "2") (pinfunction "2_2") (pintype "passive"))
    )
    (net (code "31") (name "Net-(Q2-PadC)") (class "Default")
      (node (ref "Q2") (pin "C") (pintype "passive"))
      (node (ref "R9") (pin "1") (pinfunction "1_1") (pintype "passive"))
    )
    (net (code "32") (name "Net-(R18-Pad1)") (class "Default")
      (node (ref "R18") (pin "1") (pinfunction "1_1") (pintype "passive"))
      (node (ref "R19") (pin "2") (pinfunction "2_2") (pintype "passive"))
      (node (ref "R21") (pin "2") (pinfunction "2_2") (pintype "passive"))
    )
    (net (code "33") (name "Net-(TrET1-RXN)") (class "Default")
      (node (ref "C21") (pin "1") (pintype "passive"))
      (node (ref "R26") (pin "1") (pinfunction "1_1") (pintype "passive"))
      (node (ref "TrET1") (pin "3") (pinfunction "RXN_3") (pintype "passive"))
      (node (ref "U3") (pin "22") (pinfunction "RXN_22") (pintype "passive"))
    )
    (net (code "34") (name "Net-(TrET1-RXP)") (class "Default")
      (node (ref "C20") (pin "1") (pintype "passive"))
      (node (ref "R25") (pin "1") (pinfunction "1_1") (pintype "passive"))
      (node (ref "TrET1") (pin "2") (pinfunction "RXP_2") (pintype "passive"))
      (node (ref "U3") (pin "23") (pinfunction "RXP_23") (pintype "passive"))
    )
    (net (code "35") (name "Net-(TrET1-Rx1+)") (class "Default")
      (node (ref "R28") (pin "2") (pinfunction "2_2") (pintype "passive"))
      (node (ref "TrET1") (pin "11") (pinfunction "Rx1+_11") (pintype "passive"))
    )
    (net (code "36") (name "Net-(TrET1-Rx1-)") (class "Default")
      (node (ref "J1") (pin "2") (pintype "passive"))
      (node (ref "TrET1") (pin "10") (pinfunction "Rx1-_10") (pintype "passive"))
    )
    (net (code "37") (name "Net-(TrET1-RxC1)") (class "Default")
      (node (ref "J1") (pin "1") (pintype "passive"))
      (node (ref "TrET1") (pin "12") (pinfunction "RxC1_12") (pintype "passive"))
    )
    (net (code "38") (name "Net-(TrET1-TCT1)") (class "Default")
      (node (ref "J1") (pin "6") (pintype "passive"))
      (node (ref "TrET1") (pin "7") (pinfunction "TCT1_7") (pintype "passive"))
    )
    (net (code "39") (name "Net-(TrET1-TXN)") (class "Default")
      (node (ref "C19") (pin "1") (pintype "passive"))
      (node (ref "R24") (pin "1") (pinfunction "1_1") (pintype "passive"))
      (node (ref "TrET1") (pin "5") (pinfunction "TXN_5") (pintype "passive"))
      (node (ref "U3") (pin "20") (pinfunction "TXN_20") (pintype "passive"))
    )
    (net (code "40") (name "Net-(TrET1-TXP)") (class "Default")
      (node (ref "C18") (pin "1") (pintype "passive"))
      (node (ref "R23") (pin "1") (pinfunction "1_1") (pintype "passive"))
      (node (ref "TrET1") (pin "4") (pinfunction "TXP_4") (pintype "passive"))
      (node (ref "U3") (pin "21") (pinfunction "TXP_21") (pintype "passive"))
    )
    (net (code "41") (name "Net-(TrET1-Tx1+)") (class "Default")
      (node (ref "J1") (pin "3") (pintype "passive"))
      (node (ref "TrET1") (pin "9") (pinfunction "Tx1+_9") (pintype "passive"))
    )
    (net (code "42") (name "Net-(TrET1-Tx1-)") (class "Default")
      (node (ref "R33") (pin "2") (pinfunction "2_2") (pintype "passive"))
      (node (ref "TrET1") (pin "8") (pinfunction "Tx1-_8") (pintype "passive"))
    )
    (net (code "43") (name "Net-(U2-BST)") (class "Default")
      (node (ref "R14") (pin "2") (pinfunction "2_2") (pintype "passive"))
      (node (ref "U2") (pin "6") (pinfunction "BST_6") (pintype "passive"))
    )
    (net (code "44") (name "Net-(U2-EN)") (class "Default")
      (node (ref "R17") (pin "1") (pinfunction "1_1") (pintype "passive"))
      (node (ref "U2") (pin "5") (pinfunction "EN_5") (pintype "passive"))
    )
    (net (code "45") (name "Net-(U2-FB)") (class "Default")
      (node (ref "R18") (pin "2") (pinfunction "2_2") (pintype "passive"))
      (node (ref "U2") (pin "4") (pinfunction "FB_4") (pintype "passive"))
    )
    (net (code "46") (name "Net-(U2-SW)") (class "Default")
      (node (ref "C7") (pin "1") (pinfunction "1_1") (pintype "passive"))
      (node (ref "L2") (pin "1") (pinfunction "1_1") (pintype "passive"))
      (node (ref "U2") (pin "2") (pinfunction "SW_2") (pintype "passive"))
    )
    (net (code "47") (name "Net-(U3-CRS_DV{slash}MODE2)") (class "Default")
      (node (ref "R134") (pin "2") (pinfunction "2_2") (pintype "passive"))
      (node (ref "R31") (pin "1") (pinfunction "1_1") (pintype "passive"))
      (node (ref "U3") (pin "11") (pinfunction "CRS_DV/MODE2_11") (pintype "passive"))
    )
    (net (code "48") (name "Net-(U3-RBSS)") (class "Default")
      (node (ref "R37") (pin "2") (pinfunction "2_2") (pintype "passive"))
      (node (ref "U3") (pin "24") (pinfunction "RBSS_24") (pintype "passive"))
    )
    (net (code "49") (name "Net-(U3-RXD0{slash}MODE0)") (class "Default")
      (node (ref "R132") (pin "2") (pinfunction "2_2") (pintype "passive"))
      (node (ref "R29") (pin "1") (pinfunction "1_1") (pintype "passive"))
      (node (ref "TP53") (pin "1") (pinfunction "1_1") (pintype "passive"))
      (node (ref "U3") (pin "8") (pinfunction "RXD0/MODE0_8") (pintype "passive"))
    )
    (net (code "50") (name "Net-(U3-RXD1{slash}MODE1)") (class "Default")
      (node (ref "R30") (pin "1") (pinfunction "1_1") (pintype "passive"))
      (node (ref "TP54") (pin "1") (pinfunction "1_1") (pintype "passive"))
      (node (ref "U3") (pin "7") (pinfunction "RXD1/MODE1_7") (pintype "passive"))
    )
    (net (code "51") (name "Net-(U3-VDD2A)") (class "Default")
      (node (ref "C11") (pin "1") (pintype "passive"))
      (node (ref "C12") (pin "1") (pinfunction "1_1") (pintype "passive"))
      (node (ref "C14") (pin "1") (pintype "passive"))
      (node (ref "L3") (pin "2") (pinfunction "2_2") (pintype "passive"))
      (node (ref "R23") (pin "2") (pinfunction "2_2") (pintype "passive"))
      (node (ref "R24") (pin "2") (pinfunction "2_2") (pintype "passive"))
      (node (ref "R25") (pin "2") (pinfunction "2_2") (pintype "passive"))
      (node (ref "R26") (pin "2") (pinfunction "2_2") (pintype "passive"))
      (node (ref "U3") (pin "1") (pinfunction "VDD2A_1") (pintype "passive"))
      (node (ref "U3") (pin "19") (pinfunction "VIN50_19") (pintype "passive"))
    )
    (net (code "52") (name "Net-(U3-VDDCR)") (class "Default")
      (node (ref "C16") (pin "2") (pinfunction "2_2") (pintype "passive"))
      (node (ref "C17") (pin "1") (pintype "passive"))
      (node (ref "U3") (pin "6") (pinfunction "VDDCR_6") (pintype "passive"))
    )
    (net (code "53") (name "Net-(U3-XTAL)") (class "Default")
      (node (ref "C25") (pin "1") (pintype "passive"))
      (node (ref "TP3") (pin "1") (pinfunction "1_1") (pintype "passive"))
      (node (ref "U3") (pin "4") (pinfunction "XTAL_4") (pintype "passive"))
      (node (ref "Y1") (pin "1") (pintype "passive"))
    )
    (net (code "54") (name "Net-(U3-XTAL1)") (class "Default")
      (node (ref "C26") (pin "1") (pintype "passive"))
      (node (ref "TP2") (pin "1") (pinfunction "1_1") (pintype "passive"))
      (node (ref "U3") (pin "5") (pinfunction "XTAL1_5") (pintype "passive"))
      (node (ref "Y1") (pin "3") (pintype "passive"))
    )
    (net (code "55") (name "Net-(U3-nRTS)") (class "Default")
      (node (ref "C24") (pin "1") (pintype "passive"))
      (node (ref "R36") (pin "1") (pinfunction "1_1") (pintype "passive"))
      (node (ref "U3") (pin "15") (pinfunction "nRTS_15") (pintype "passive"))
    )
    (net (code "56") (name "VCC=3.3V") (class "Default")
      (node (ref "C10") (pin "1") (pinfunction "1_1") (pintype "passive"))
      (node (ref "C13") (pin "1") (pintype "passive"))
      (node (ref "C15") (pin "1") (pinfunction "1_1") (pintype "passive"))
      (node (ref "C23") (pin "1") (pintype "passive"))
      (node (ref "D5") (pin "A") (pinfunction "A_A") (pintype "passive"))
      (node (ref "L2") (pin "2") (pinfunction "2_2") (pintype "passive"))
      (node (ref "L3") (pin "1") (pinfunction "1_1") (pintype "passive"))
      (node (ref "R130") (pin "2") (pinfunction "2_2") (pintype "passive"))
      (node (ref "R131") (pin "2") (pinfunction "2_2") (pintype "passive"))
      (node (ref "R132") (pin "1") (pinfunction "1_1") (pintype "passive"))
      (node (ref "R133") (pin "1") (pinfunction "1_1") (pintype "passive"))
      (node (ref "R134") (pin "1") (pinfunction "1_1") (pintype "passive"))
      (node (ref "R19") (pin "1") (pinfunction "1_1") (pintype "passive"))
      (node (ref "R20") (pin "1") (pinfunction "1_1") (pintype "passive"))
      (node (ref "R22") (pin "2") (pinfunction "2_2") (pintype "passive"))
      (node (ref "R36") (pin "2") (pinfunction "2_2") (pintype "passive"))
      (node (ref "TP1") (pin "1") (pinfunction "1_1") (pintype "passive"))
      (node (ref "TrET1") (pin "1") (pinfunction "Vcc_1") (pintype "passive"))
      (node (ref "TrET1") (pin "6") (pinfunction "Vcc_6") (pintype "passive"))
      (node (ref "U3") (pin "9") (pinfunction "VDDIO_9") (pintype "passive"))
    )
    (net (code "57") (name "VCC=12V") (class "Default")
      (node (ref "D16") (pin "1") (pinfunction "A_1") (pintype "passive"))
      (node (ref "D2") (pin "1") (pinfunction "A_1") (pintype "passive"))
      (node (ref "R3") (pin "2") (pinfunction "2_2") (pintype "passive"))
      (node (ref "R4") (pin "2") (pinfunction "2_2") (pintype "passive"))
    )
    (net (code "58") (name "unconnected-(R133-Pad2)") (class "Default")
      (node (ref "R133") (pin "2") (pinfunction "2_2") (pintype "passive"))
    )
  )
)
